# temperature.net
KiCad netlist of a schematic drawn in Altium Designer
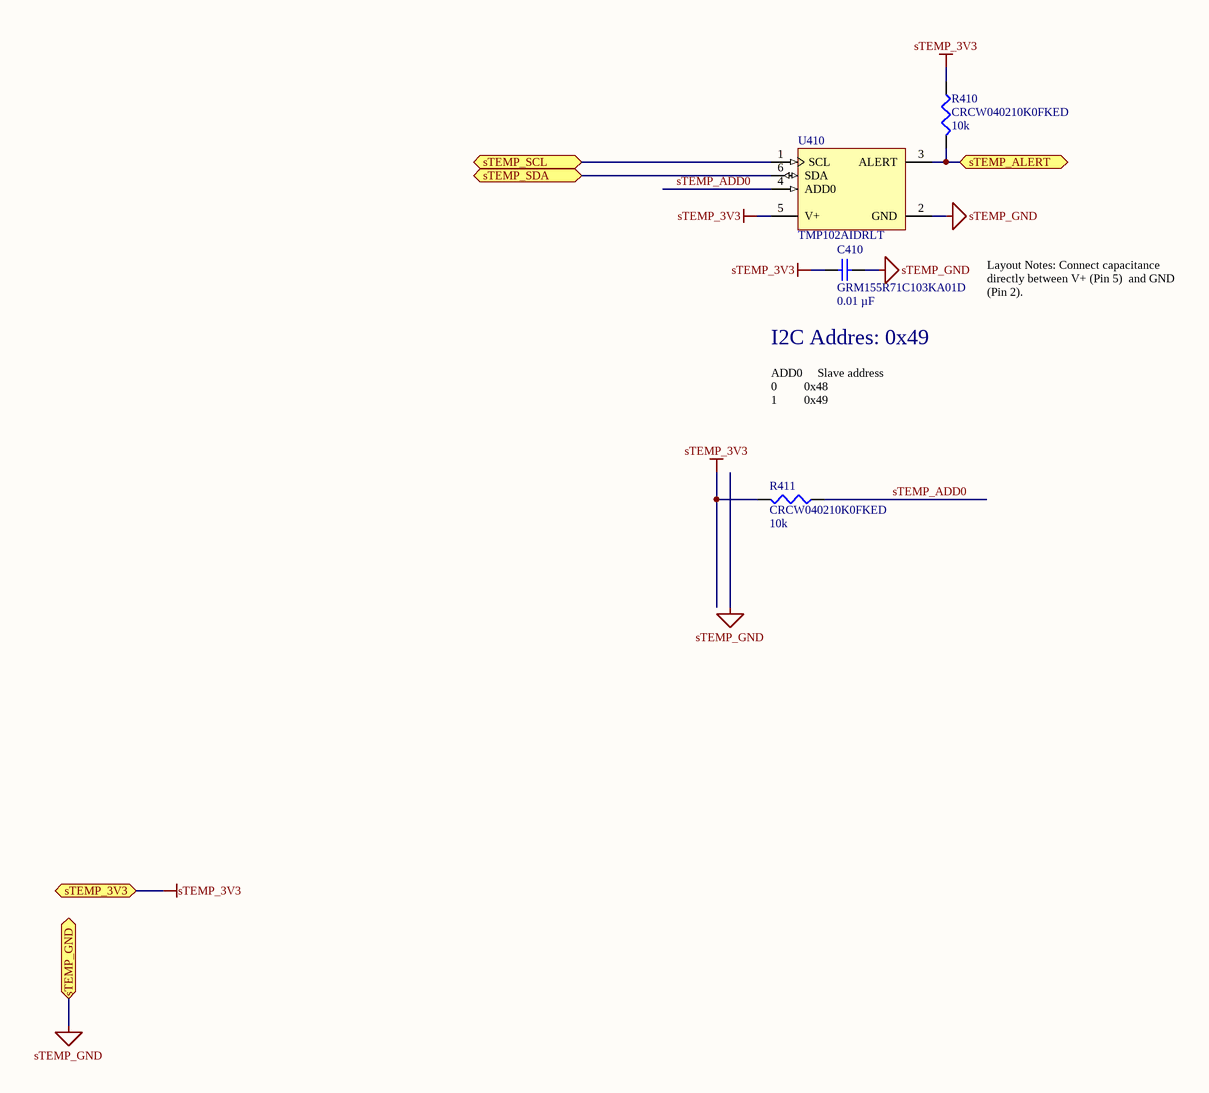
[diagram p0: _temperature.SchDoc]

(export (version "E")
  (design (tool "Eeschema 10.0.6"))
  (components
    (comp (ref "C410")
      (value "GRM155R71C103KA01D")
      (footprint "0402")
      (description "Cap, 0.01 µF, 16 V, X7R")
      (fields (field (name "ALTIUM_VALUE") "0.01 µF") (field (name "PUBLISHER") "Altium Limited"))
      (libsource (lib "miscellaneous_devices") (part "Cap"))
    )
    (comp (ref "R410")
      (value "CRCW040210K0FKED")
      (footprint "0402")
      (description "0.125W, -55-155C, 1005, 50V, ±1%")
      (fields (field (name "ALTIUM_VALUE") "10k"))
      (libsource (lib "standard_resistors") (part "CRCW0402xxxxFKED"))
    )
    (comp (ref "R411")
      (value "CRCW040210K0FKED")
      (footprint "0402")
      (description "0.125W, -55-155C, 1005, 50V, ±1%")
      (fields (field (name "ALTIUM_VALUE") "10k"))
      (libsource (lib "standard_resistors") (part "CRCW0402xxxxFKED"))
    )
    (comp (ref "U410")
      (value "TMP102AIDRLT")
      (footprint "DRL0006A_L")
      (libsource (lib "Altium Content Vault") (part "TI-TMP102AIDRLT-DRL6"))
    )
  )
  (nets
    (net (code "1") (name "/sTEMP_ADD0") (class "Default")
      (node (ref "R411") (pin "1") (pinfunction "1_1") (pintype "passive"))
      (node (ref "U410") (pin "4") (pinfunction "ADD0_4") (pintype "input"))
    )
    (net (code "2") (name "/sTEMP_ALERT") (class "Default")
      (node (ref "R410") (pin "2") (pinfunction "2_2") (pintype "passive"))
      (node (ref "U410") (pin "3") (pinfunction "ALERT_3") (pintype "open_collector"))
    )
    (net (code "3") (name "/sTEMP_SCL") (class "Default")
      (node (ref "U410") (pin "1") (pinfunction "SCL_1") (pintype "input"))
    )
    (net (code "4") (name "/sTEMP_SDA") (class "Default")
      (node (ref "U410") (pin "6") (pinfunction "SDA_6") (pintype "bidirectional"))
    )
    (net (code "5") (name "sTEMP_3V3") (class "Default")
      (node (ref "C410") (pin "2") (pinfunction "2_2") (pintype "passive"))
      (node (ref "R410") (pin "1") (pinfunction "1_1") (pintype "passive"))
      (node (ref "R411") (pin "2") (pinfunction "2_2") (pintype "passive"))
      (node (ref "U410") (pin "5") (pinfunction "V+_5") (pintype "power_in"))
    )
    (net (code "6") (name "sTEMP_GND") (class "Default")
      (node (ref "C410") (pin "1") (pinfunction "1_1") (pintype "passive"))
      (node (ref "U410") (pin "2") (pinfunction "GND_2") (pintype "power_in"))
    )
  )
)
